# v3s-v0_1_0.net
KiCad netlist of a schematic drawn in EAGLE
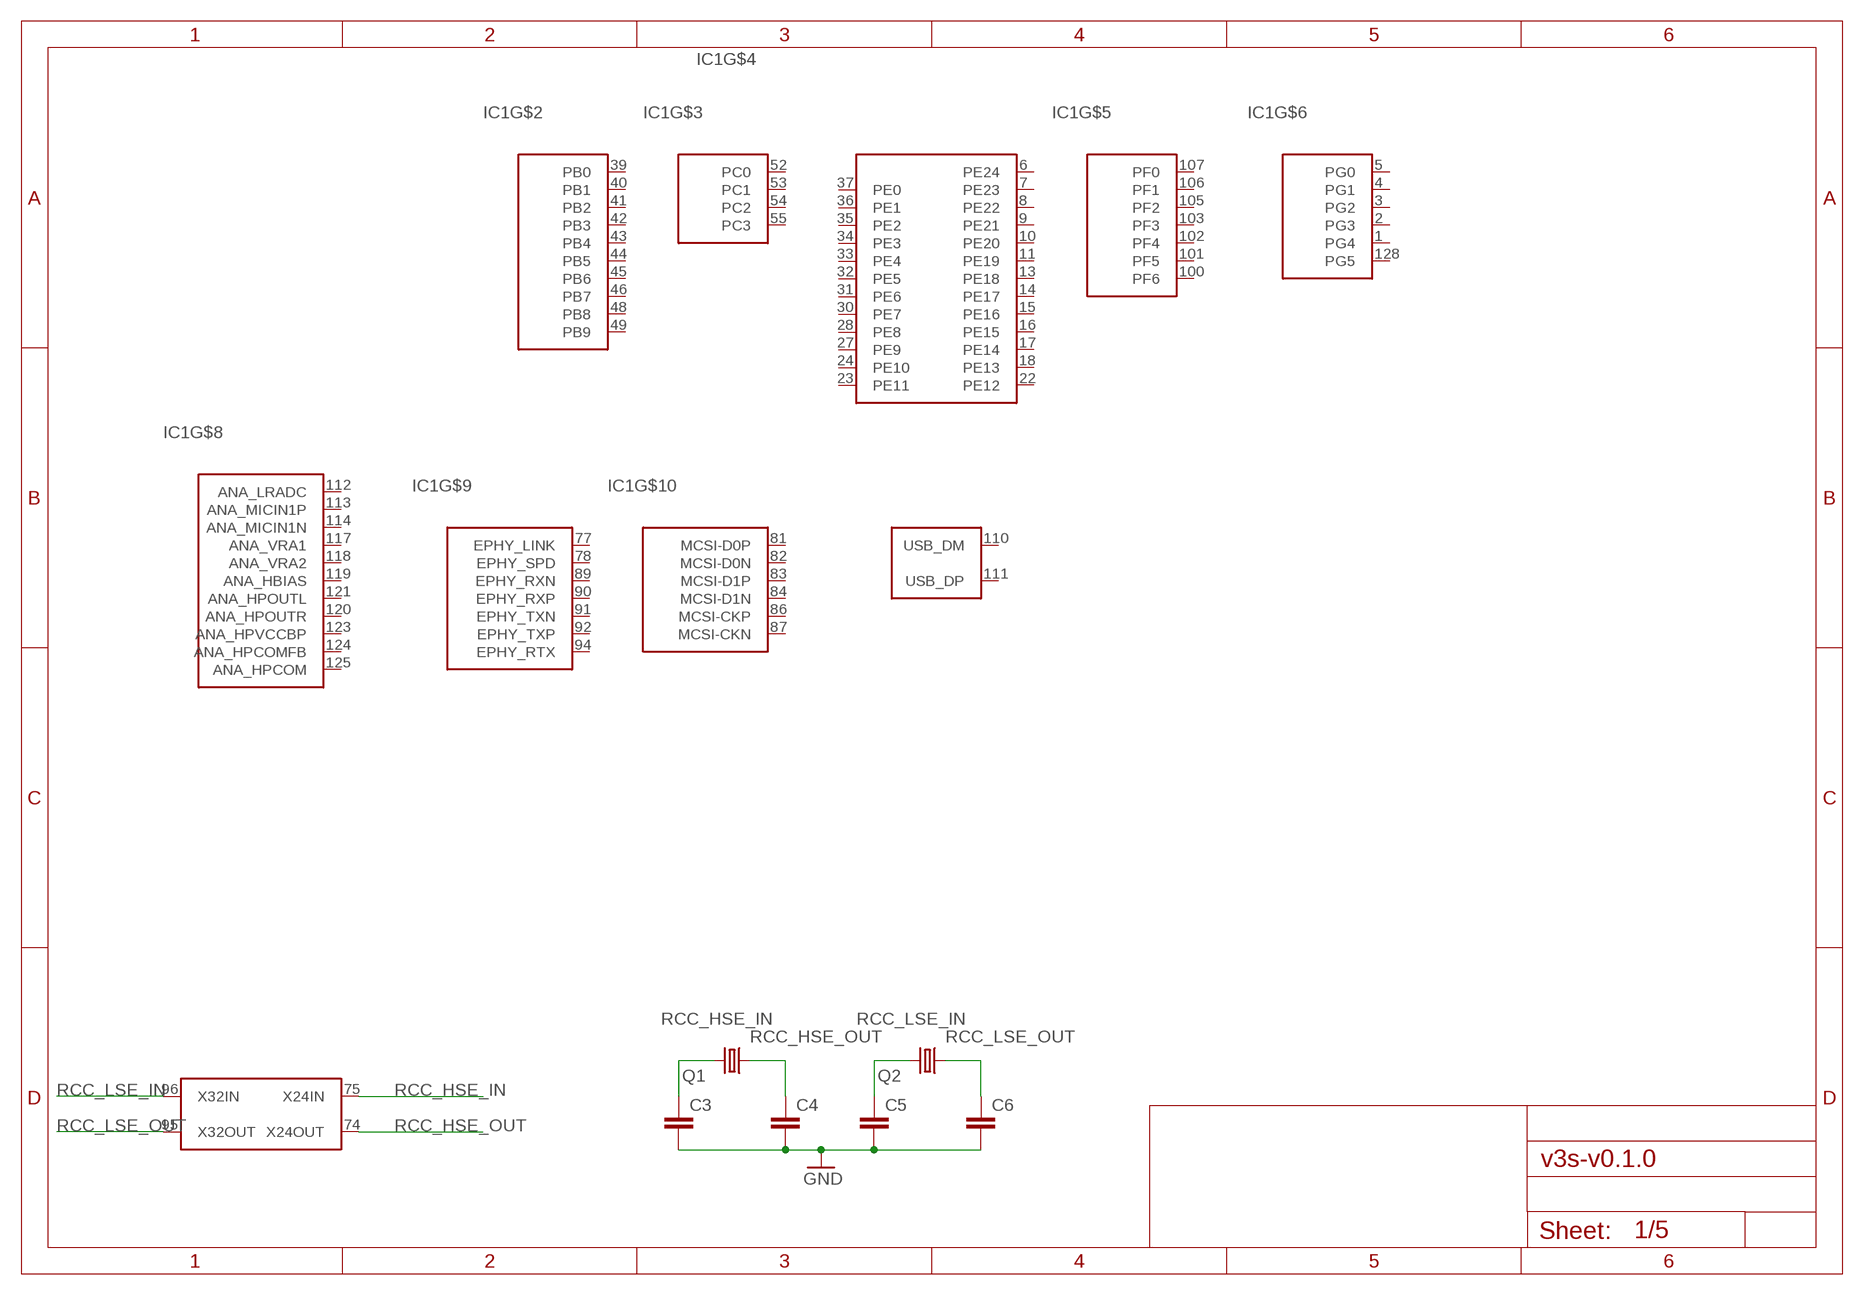
[diagram p0: schematic, sheet 1]
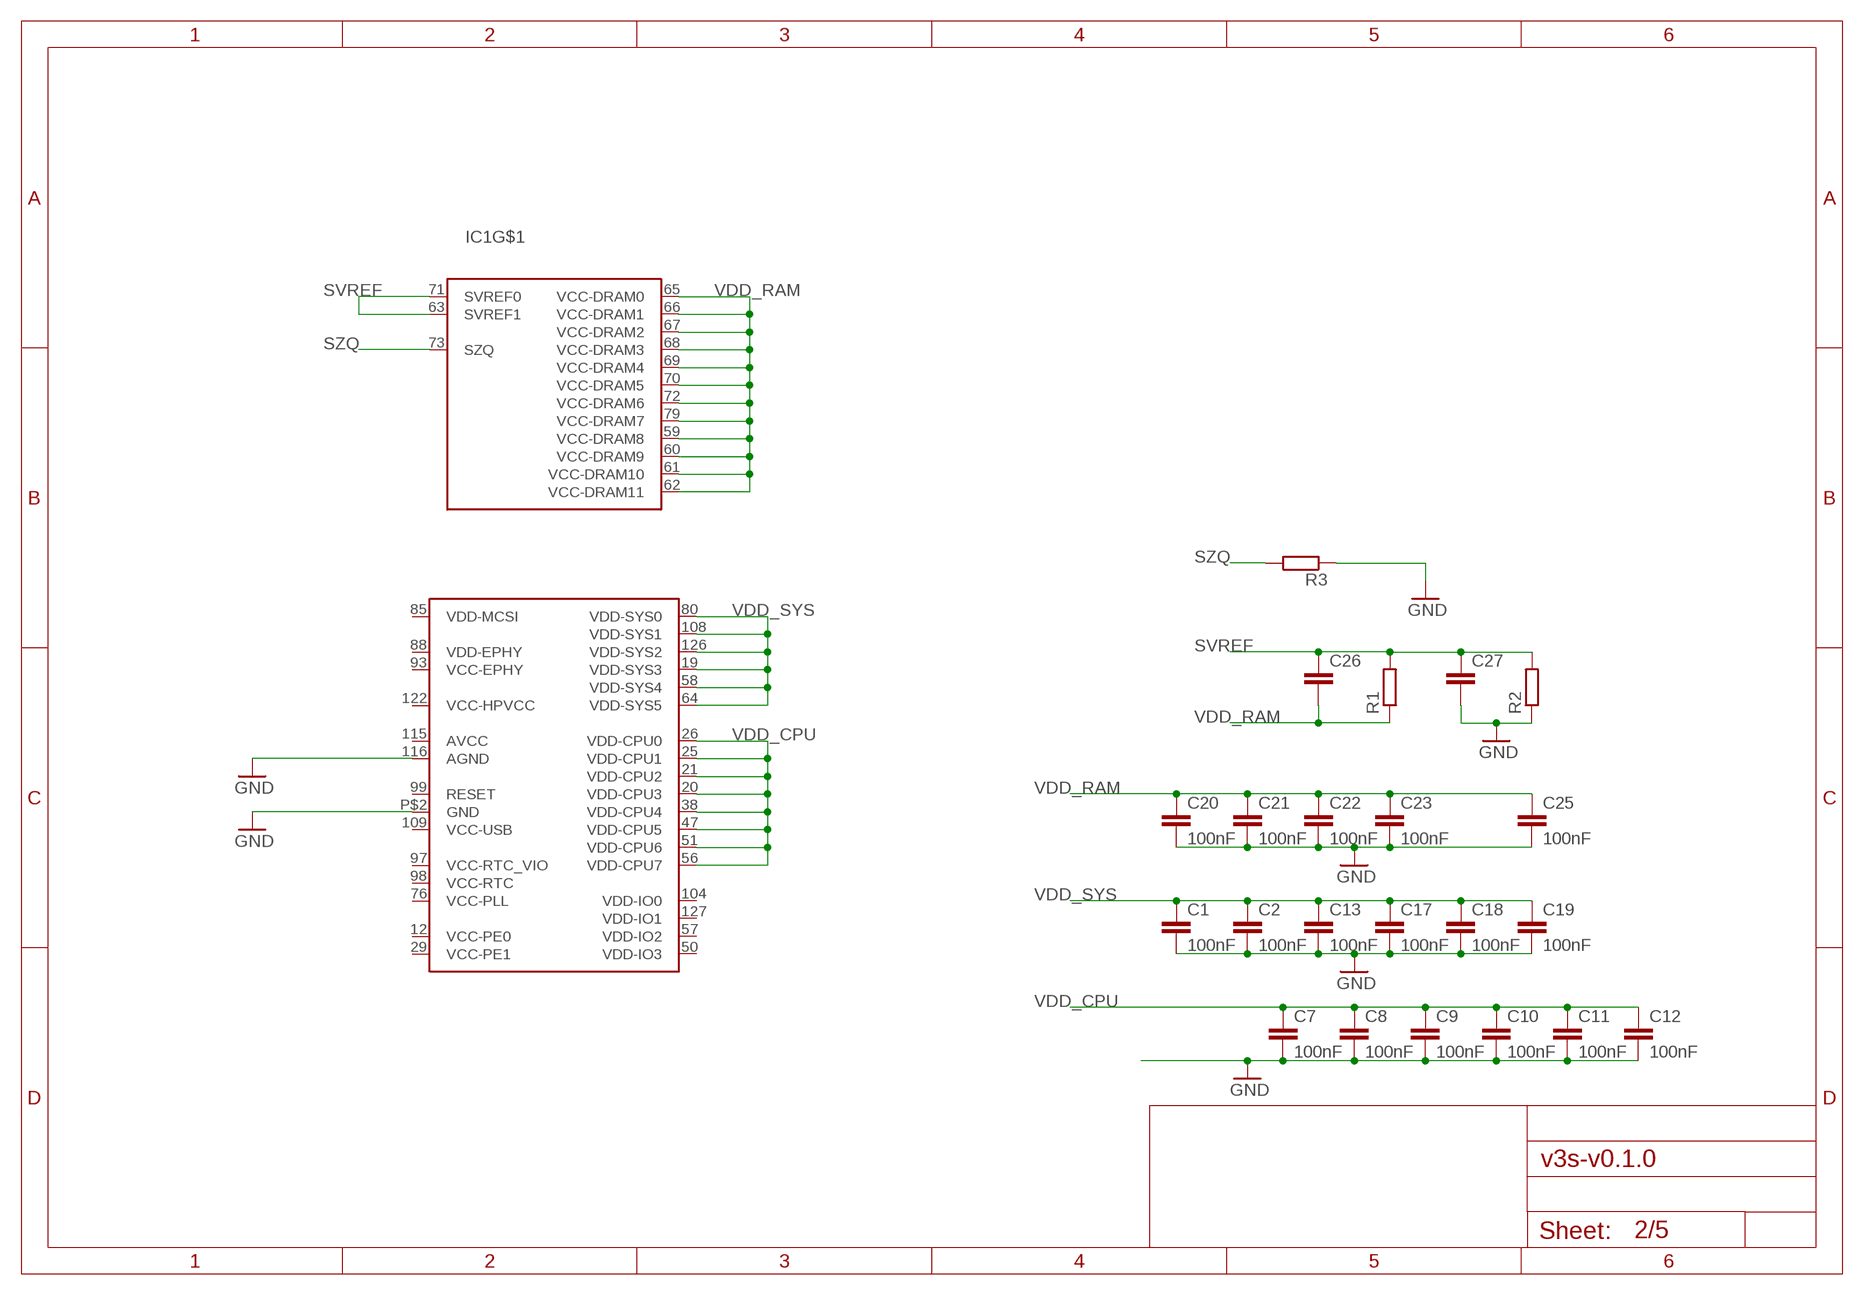
[diagram p1: schematic, sheet 2]
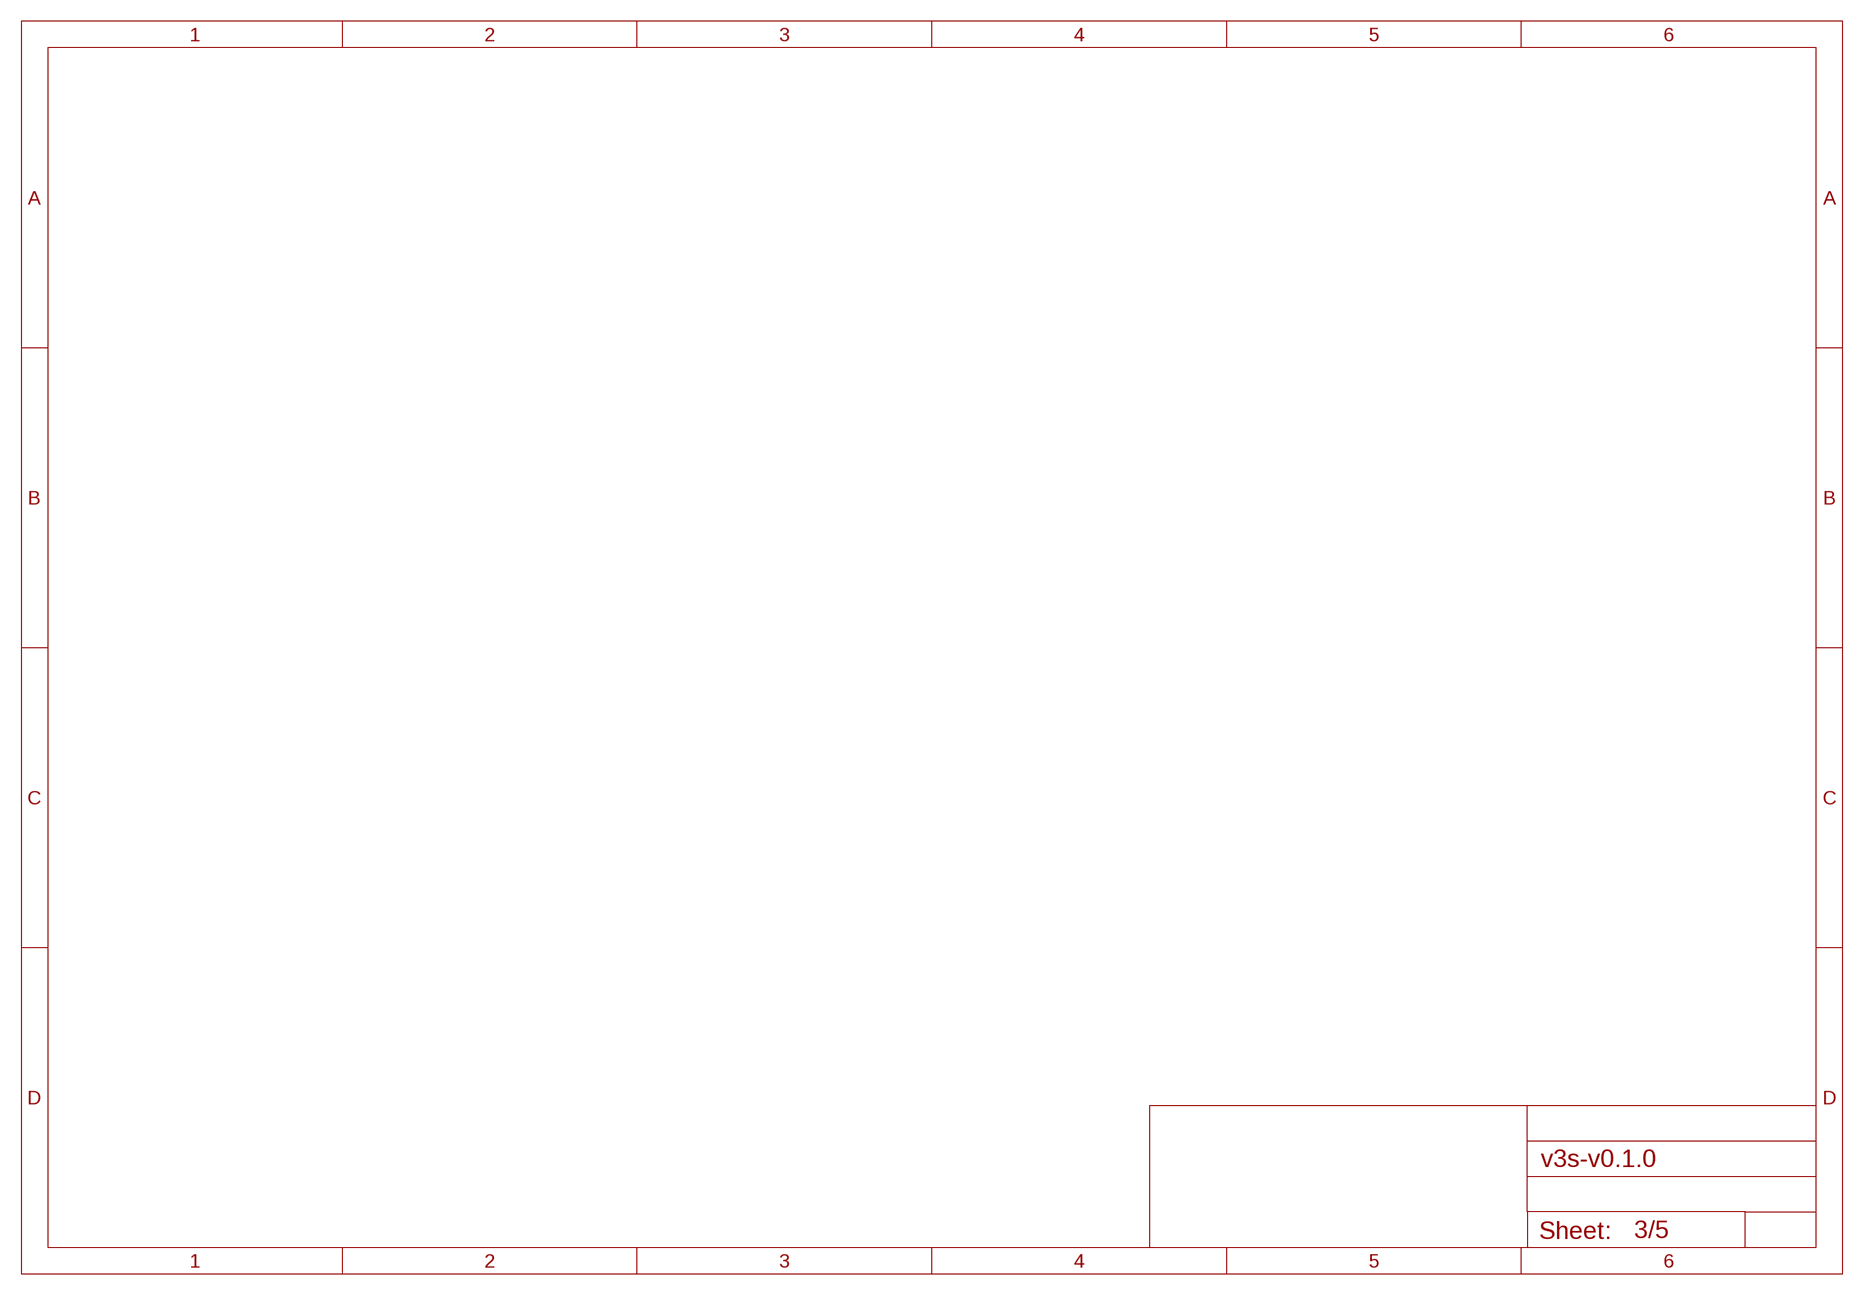
[diagram p2: schematic, sheet 3]
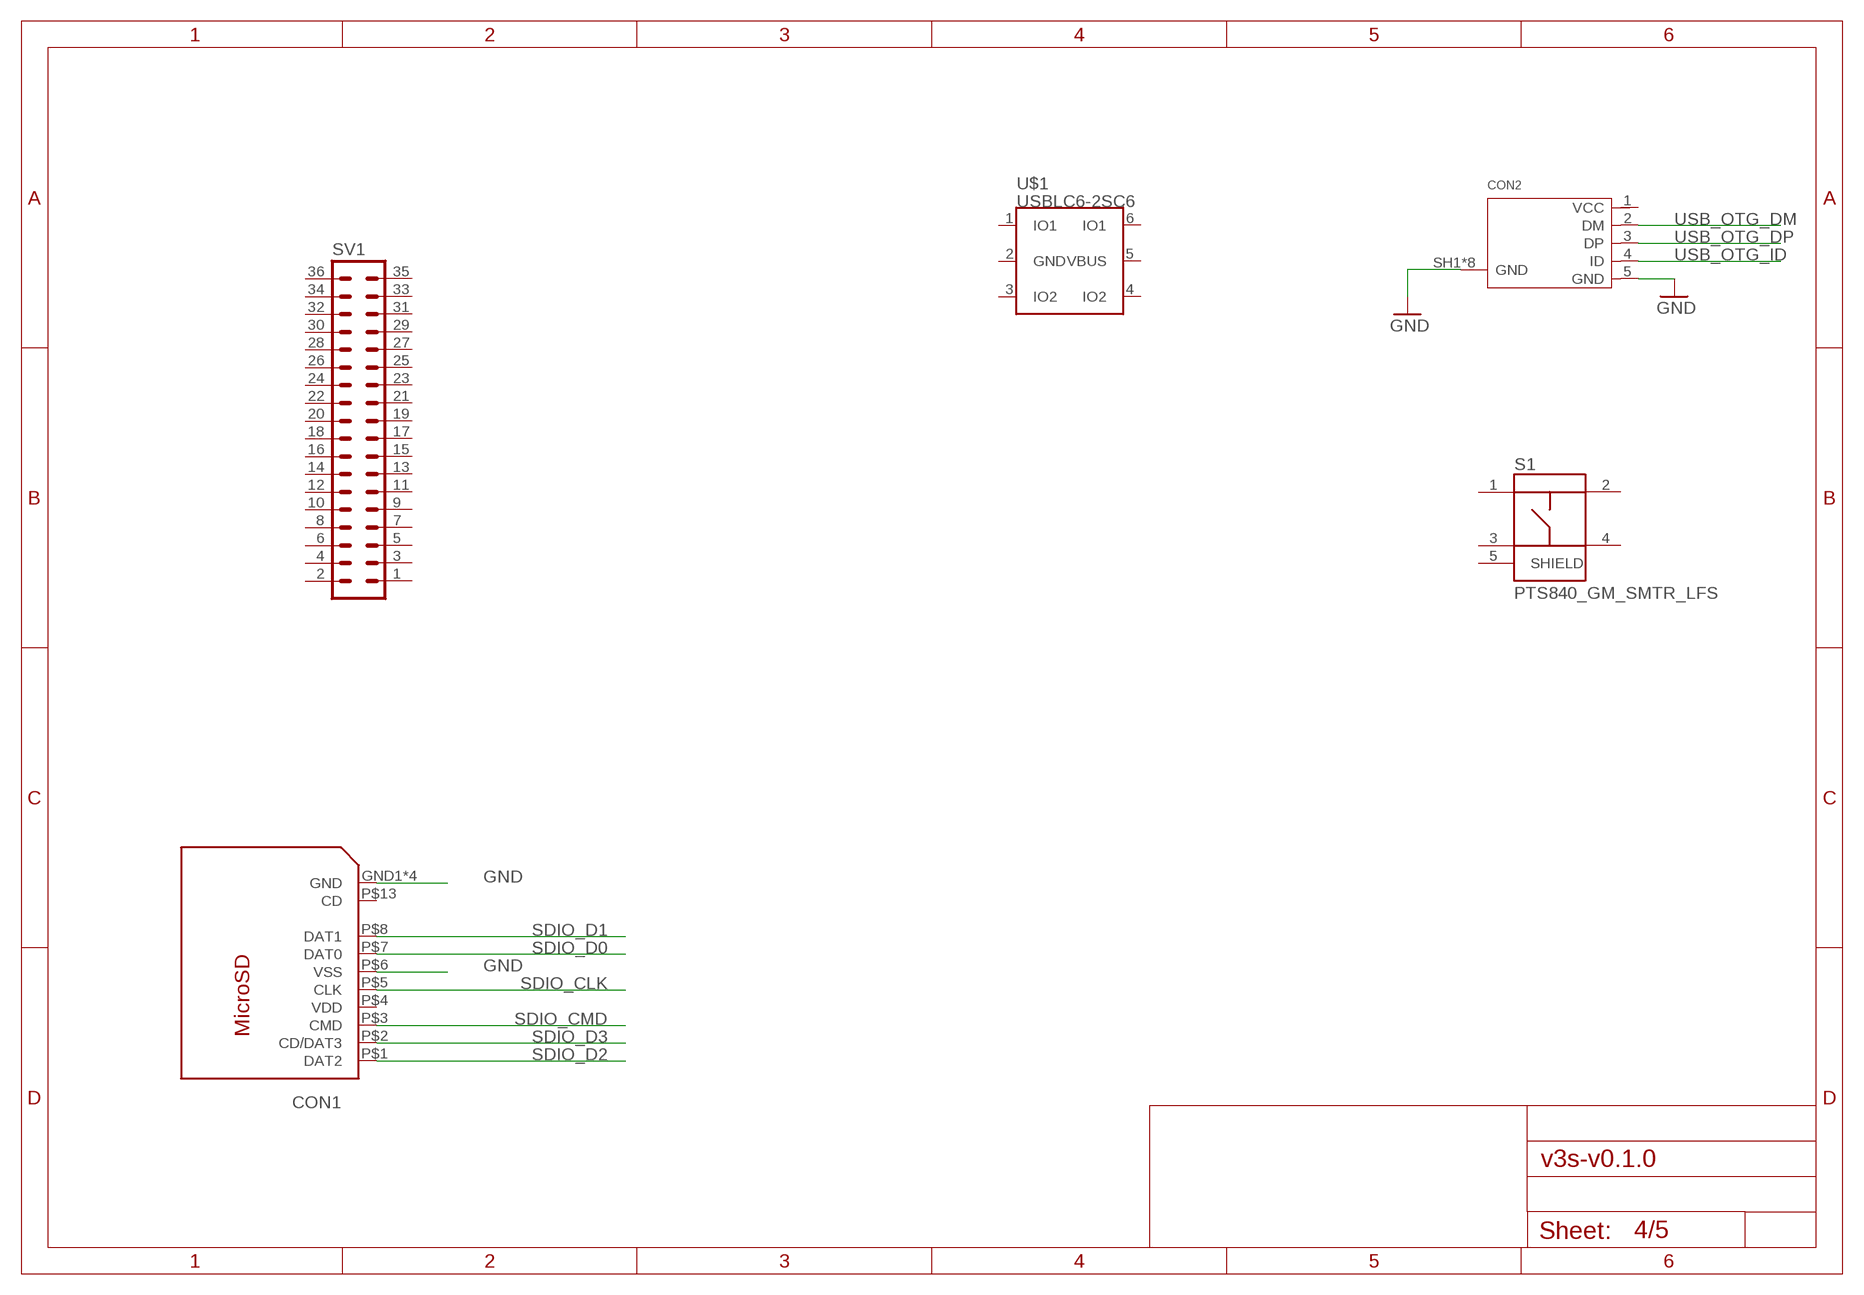
[diagram p3: schematic, sheet 4]
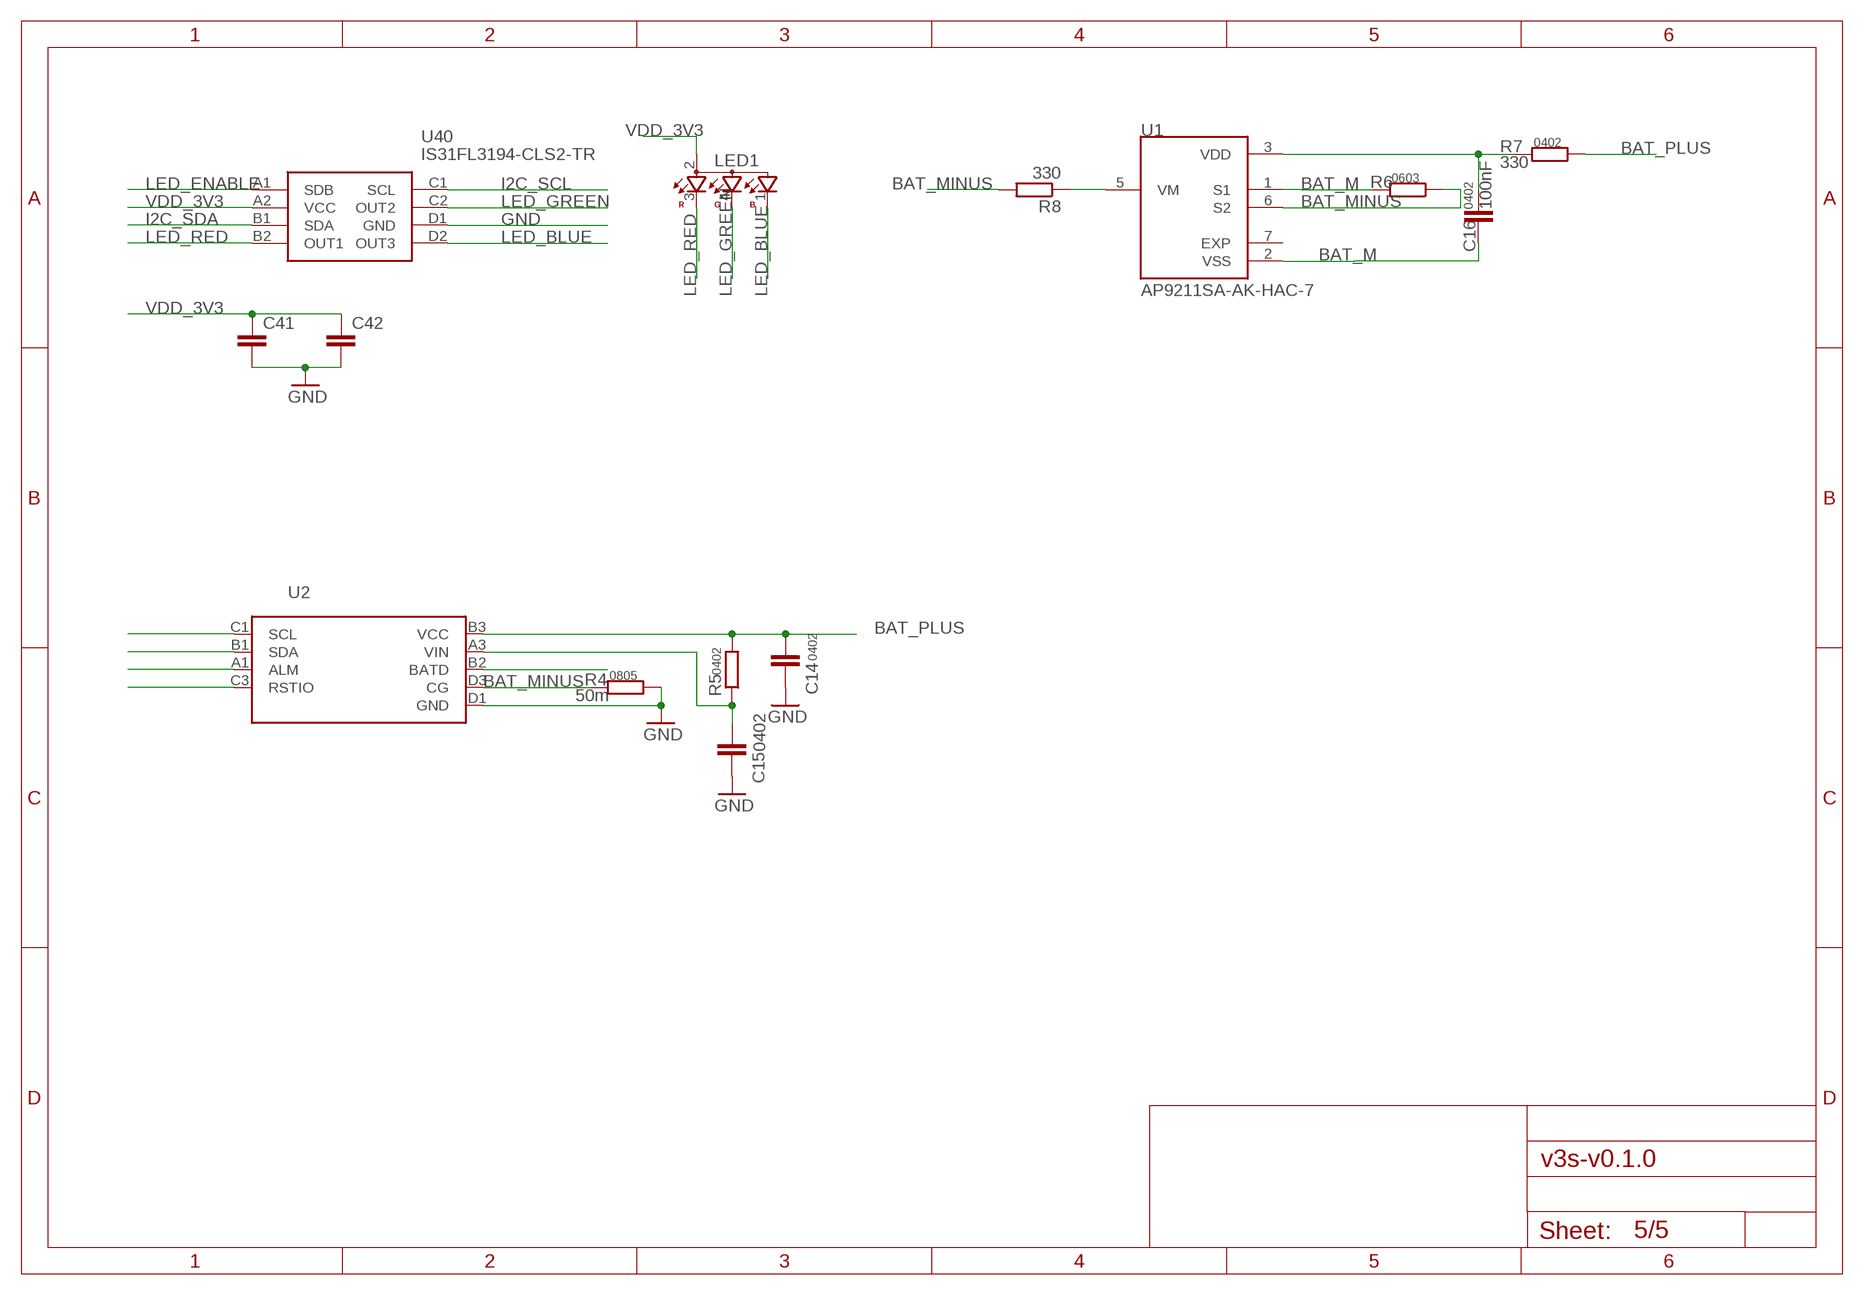
[diagram p4: schematic, sheet 5]

(export (version "E")
  (design (tool "Eeschema 10.0.6"))
  (components
    (comp (ref "CON1")
      (value "112J-TXAR")
      (footprint "eagle-import:112J")
      (libsource (lib "eagle-import") (part "112J-TXAR"))
    )
    (comp (ref "CON2")
      (value "10118194-0001LF")
      (footprint "eagle-import:10118194")
      (libsource (lib "eagle-import") (part "10118194-0001LF"))
    )
    (comp (ref "S1")
      (value "PTS840_GM_SMTR_LFS")
      (footprint "eagle-import:SW_PTS840GMSMTRLFS")
      (fields (field (name "MF") "C&K") (field (name "MP") "PTS840 GM SMTR LFS"))
      (libsource (lib "eagle-import") (part "PTS840_GM_SMTR_LFS"))
    )
    (comp (ref "SV1")
      (value "MA18-2")
      (footprint "eagle-import:MA18-2")
      (libsource (lib "eagle-import") (part "MA18-2"))
    )
    (comp (ref "U$1")
      (value "USBLC6-2SC6")
      (footprint "eagle-import:SOT95P280X110-6")
      (libsource (lib "eagle-import") (part "USBLC6-2SC6"))
    )
    (comp (ref "C1")
      (value "100nF")
      (footprint "eagle-import:C0402")
      (libsource (lib "eagle-import") (part "C-EUC0402"))
    )
    (comp (ref "C2")
      (value "100nF")
      (footprint "eagle-import:C0402")
      (libsource (lib "eagle-import") (part "C-EUC0402"))
    )
    (comp (ref "C7")
      (value "100nF")
      (footprint "eagle-import:C0402")
      (libsource (lib "eagle-import") (part "C-EUC0402"))
    )
    (comp (ref "C8")
      (value "100nF")
      (footprint "eagle-import:C0402")
      (libsource (lib "eagle-import") (part "C-EUC0402"))
    )
    (comp (ref "C9")
      (value "100nF")
      (footprint "eagle-import:C0402")
      (libsource (lib "eagle-import") (part "C-EUC0402"))
    )
    (comp (ref "C10")
      (value "100nF")
      (footprint "eagle-import:C0402")
      (libsource (lib "eagle-import") (part "C-EUC0402"))
    )
    (comp (ref "C11")
      (value "100nF")
      (footprint "eagle-import:C0402")
      (libsource (lib "eagle-import") (part "C-EUC0402"))
    )
    (comp (ref "C12")
      (value "100nF")
      (footprint "eagle-import:C0402")
      (libsource (lib "eagle-import") (part "C-EUC0402"))
    )
    (comp (ref "C13")
      (value "100nF")
      (footprint "eagle-import:C0402")
      (libsource (lib "eagle-import") (part "C-EUC0402"))
    )
    (comp (ref "C17")
      (value "100nF")
      (footprint "eagle-import:C0402")
      (libsource (lib "eagle-import") (part "C-EUC0402"))
    )
    (comp (ref "C18")
      (value "100nF")
      (footprint "eagle-import:C0402")
      (libsource (lib "eagle-import") (part "C-EUC0402"))
    )
    (comp (ref "C19")
      (value "100nF")
      (footprint "eagle-import:C0402")
      (libsource (lib "eagle-import") (part "C-EUC0402"))
    )
    (comp (ref "C20")
      (value "100nF")
      (footprint "eagle-import:C0402")
      (libsource (lib "eagle-import") (part "C-EUC0402"))
    )
    (comp (ref "C21")
      (value "100nF")
      (footprint "eagle-import:C0402")
      (libsource (lib "eagle-import") (part "C-EUC0402"))
    )
    (comp (ref "C22")
      (value "100nF")
      (footprint "eagle-import:C0402")
      (libsource (lib "eagle-import") (part "C-EUC0402"))
    )
    (comp (ref "C23")
      (value "100nF")
      (footprint "eagle-import:C0402")
      (libsource (lib "eagle-import") (part "C-EUC0402"))
    )
    (comp (ref "C25")
      (value "100nF")
      (footprint "eagle-import:C0402")
      (libsource (lib "eagle-import") (part "C-EUC0402"))
    )
    (comp (ref "C26")
      (value "C-EUC0402")
      (footprint "eagle-import:C0402")
      (libsource (lib "eagle-import") (part "C-EUC0402"))
    )
    (comp (ref "C27")
      (value "C-EUC0402")
      (footprint "eagle-import:C0402")
      (libsource (lib "eagle-import") (part "C-EUC0402"))
    )
    (comp (ref "IC1")
      (value "V3S")
      (footprint "eagle-import:QFP-128")
      (libsource (lib "eagle-import") (part "V3S"))
    )
    (comp (ref "R1")
      (value "R-EU_R0402")
      (footprint "eagle-import:R0402")
      (libsource (lib "eagle-import") (part "R-EU_R0402"))
    )
    (comp (ref "R2")
      (value "R-EU_R0402")
      (footprint "eagle-import:R0402")
      (libsource (lib "eagle-import") (part "R-EU_R0402"))
    )
    (comp (ref "R3")
      (value "R-EU_R0402")
      (footprint "eagle-import:R0402")
      (libsource (lib "eagle-import") (part "R-EU_R0402"))
    )
    (comp (ref "C14")
      (value "C-EUC0402")
      (footprint "eagle-import:C0402")
      (libsource (lib "eagle-import") (part "C-EUC0402"))
    )
    (comp (ref "C15")
      (value "C-EUC0402")
      (footprint "eagle-import:C0402")
      (libsource (lib "eagle-import") (part "C-EUC0402"))
    )
    (comp (ref "C16")
      (value "100nF")
      (footprint "eagle-import:C0402")
      (libsource (lib "eagle-import") (part "C-EUC0402"))
    )
    (comp (ref "C41")
      (value "C-EUC0402")
      (footprint "eagle-import:C0402")
      (libsource (lib "eagle-import") (part "C-EUC0402"))
    )
    (comp (ref "C42")
      (value "C-EUC0402")
      (footprint "eagle-import:C0402")
      (libsource (lib "eagle-import") (part "C-EUC0402"))
    )
    (comp (ref "LED1")
      (value "OSTB1204C1E")
      (footprint "eagle-import:321015RGB")
      (libsource (lib "eagle-import") (part "OSTB1204C1E"))
    )
    (comp (ref "R4")
      (value "50m")
      (footprint "eagle-import:R0805")
      (libsource (lib "eagle-import") (part "R-EU_R0805"))
    )
    (comp (ref "R5")
      (value "R-EU_R0402")
      (footprint "eagle-import:R0402")
      (libsource (lib "eagle-import") (part "R-EU_R0402"))
    )
    (comp (ref "R6")
      (value "R-EU_R0603")
      (footprint "eagle-import:R0603")
      (libsource (lib "eagle-import") (part "R-EU_R0603"))
    )
    (comp (ref "R7")
      (value "330")
      (footprint "eagle-import:R0402")
      (libsource (lib "eagle-import") (part "R-EU_R0402"))
    )
    (comp (ref "R8")
      (value "330")
      (footprint "eagle-import:R0402")
      (libsource (lib "eagle-import") (part "R-EU_R0402"))
    )
    (comp (ref "U1")
      (value "AP9211SA-AK-HAC-7")
      (footprint "eagle-import:DFN200X300X60-7N")
      (fields (field (name "MF") "Diodes Inc."))
      (libsource (lib "eagle-import") (part "AP9211SA-AK-HAC-7"))
    )
    (comp (ref "U2")
      (value "STC3115")
      (footprint "eagle-import:BGA12C40P4X3_137X201X65")
      (libsource (lib "eagle-import") (part "STC3115"))
    )
    (comp (ref "U40")
      (value "IS31FL3194-CLS2-TR")
      (footprint "eagle-import:BGA8C40P2X4_99X159X42")
      (fields (field (name "MOUSER_PART_NUMBER") "870-IS31FL3194CLS2TR"))
      (libsource (lib "eagle-import") (part "IS31FL3194-CLS2-TR"))
    )
    (comp (ref "C3")
      (value "C-EUC0402")
      (footprint "eagle-import:C0402")
      (libsource (lib "eagle-import") (part "C-EUC0402"))
    )
    (comp (ref "C4")
      (value "C-EUC0402")
      (footprint "eagle-import:C0402")
      (libsource (lib "eagle-import") (part "C-EUC0402"))
    )
    (comp (ref "C5")
      (value "C-EUC0402")
      (footprint "eagle-import:C0402")
      (libsource (lib "eagle-import") (part "C-EUC0402"))
    )
    (comp (ref "C6")
      (value "C-EUC0402")
      (footprint "eagle-import:C0402")
      (libsource (lib "eagle-import") (part "C-EUC0402"))
    )
    (comp (ref "Q1")
      (value "KX-7")
      (footprint "eagle-import:3.2X2.5_KX-7")
      (libsource (lib "eagle-import") (part "KX-7"))
    )
    (comp (ref "Q2")
      (value "KX-327-NHF")
      (footprint "eagle-import:3.2X1.5")
      (libsource (lib "eagle-import") (part "KX-327-NHF"))
    )
  )
  (nets
    (net (code "1") (name "BAT_M") (class "Default")
      (node (ref "C16") (pin "2") (pinfunction "2_2") (pintype "passive"))
      (node (ref "R6") (pin "2") (pinfunction "2_2") (pintype "passive"))
      (node (ref "U1") (pin "1") (pinfunction "S1_1") (pintype "output"))
      (node (ref "U1") (pin "2") (pinfunction "VSS_2") (pintype "power_in"))
    )
    (net (code "2") (name "BAT_MINUS") (class "Default")
      (node (ref "R4") (pin "2") (pinfunction "2_2") (pintype "passive"))
      (node (ref "R6") (pin "1") (pinfunction "1_1") (pintype "passive"))
      (node (ref "R8") (pin "2") (pinfunction "2_2") (pintype "passive"))
      (node (ref "U1") (pin "6") (pinfunction "S2_6") (pintype "output"))
      (node (ref "U2") (pin "D3") (pinfunction "CG_D3") (pintype "bidirectional"))
    )
    (net (code "3") (name "BAT_PLUS") (class "Default")
      (node (ref "C14") (pin "1") (pinfunction "1_1") (pintype "passive"))
      (node (ref "R5") (pin "2") (pinfunction "2_2") (pintype "passive"))
      (node (ref "R7") (pin "1") (pinfunction "1_1") (pintype "passive"))
      (node (ref "U2") (pin "B3") (pinfunction "VCC_B3") (pintype "bidirectional"))
    )
    (net (code "4") (name "CD") (class "Default")
      (node (ref "CON1") (pin "P$13") (pinfunction "CD_P$13") (pintype "power_in"))
    )
    (net (code "5") (name "EXP") (class "Default")
      (node (ref "U1") (pin "7") (pinfunction "EXP_7") (pintype "power_in"))
    )
    (net (code "6") (name "GND") (class "Default")
      (node (ref "C1") (pin "2") (pinfunction "2_2") (pintype "passive"))
      (node (ref "C10") (pin "2") (pinfunction "2_2") (pintype "passive"))
      (node (ref "C11") (pin "2") (pinfunction "2_2") (pintype "passive"))
      (node (ref "C12") (pin "2") (pinfunction "2_2") (pintype "passive"))
      (node (ref "C13") (pin "2") (pinfunction "2_2") (pintype "passive"))
      (node (ref "C14") (pin "2") (pinfunction "2_2") (pintype "passive"))
      (node (ref "C15") (pin "2") (pinfunction "2_2") (pintype "passive"))
      (node (ref "C17") (pin "2") (pinfunction "2_2") (pintype "passive"))
      (node (ref "C18") (pin "2") (pinfunction "2_2") (pintype "passive"))
      (node (ref "C19") (pin "2") (pinfunction "2_2") (pintype "passive"))
      (node (ref "C2") (pin "2") (pinfunction "2_2") (pintype "passive"))
      (node (ref "C20") (pin "2") (pinfunction "2_2") (pintype "passive"))
      (node (ref "C21") (pin "2") (pinfunction "2_2") (pintype "passive"))
      (node (ref "C22") (pin "2") (pinfunction "2_2") (pintype "passive"))
      (node (ref "C23") (pin "2") (pinfunction "2_2") (pintype "passive"))
      (node (ref "C25") (pin "2") (pinfunction "2_2") (pintype "passive"))
      (node (ref "C27") (pin "2") (pinfunction "2_2") (pintype "passive"))
      (node (ref "C3") (pin "2") (pinfunction "2_2") (pintype "passive"))
      (node (ref "C4") (pin "2") (pinfunction "2_2") (pintype "passive"))
      (node (ref "C41") (pin "2") (pinfunction "2_2") (pintype "passive"))
      (node (ref "C42") (pin "2") (pinfunction "2_2") (pintype "passive"))
      (node (ref "C5") (pin "2") (pinfunction "2_2") (pintype "passive"))
      (node (ref "C6") (pin "2") (pinfunction "2_2") (pintype "passive"))
      (node (ref "C7") (pin "2") (pinfunction "2_2") (pintype "passive"))
      (node (ref "C8") (pin "2") (pinfunction "2_2") (pintype "passive"))
      (node (ref "C9") (pin "2") (pinfunction "2_2") (pintype "passive"))
      (node (ref "CON1") (pin "GND1") (pinfunction "GND_GND1") (pintype "power_in"))
      (node (ref "CON1") (pin "GND2") (pinfunction "GND_GND2") (pintype "power_in"))
      (node (ref "CON1") (pin "GND3") (pinfunction "GND_GND3") (pintype "power_in"))
      (node (ref "CON1") (pin "GND4") (pinfunction "GND_GND4") (pintype "power_in"))
      (node (ref "CON1") (pin "P$6") (pinfunction "VSS_P$6") (pintype "bidirectional"))
      (node (ref "CON2") (pin "5") (pinfunction "GND_5") (pintype "bidirectional"))
      (node (ref "CON2") (pin "SH1") (pinfunction "GND_SH1") (pintype "bidirectional"))
      (node (ref "CON2") (pin "SH2") (pinfunction "GND_SH2") (pintype "bidirectional"))
      (node (ref "CON2") (pin "SH3") (pinfunction "GND_SH3") (pintype "bidirectional"))
      (node (ref "CON2") (pin "SH4") (pinfunction "GND_SH4") (pintype "bidirectional"))
      (node (ref "CON2") (pin "SH5") (pinfunction "GND_SH5") (pintype "bidirectional"))
      (node (ref "CON2") (pin "SH6") (pinfunction "GND_SH6") (pintype "bidirectional"))
      (node (ref "CON2") (pin "SH7") (pinfunction "GND_SH7") (pintype "bidirectional"))
      (node (ref "CON2") (pin "SH8") (pinfunction "GND_SH8") (pintype "bidirectional"))
      (node (ref "IC1") (pin "116") (pinfunction "AGND_116") (pintype "bidirectional"))
      (node (ref "IC1") (pin "P$2") (pinfunction "GND_P$2") (pintype "bidirectional"))
      (node (ref "R2") (pin "1") (pinfunction "1_1") (pintype "passive"))
      (node (ref "R3") (pin "1") (pinfunction "1_1") (pintype "passive"))
      (node (ref "R4") (pin "1") (pinfunction "1_1") (pintype "passive"))
      (node (ref "U2") (pin "D1") (pinfunction "GND_D1") (pintype "bidirectional"))
      (node (ref "U40") (pin "D1") (pinfunction "GND_D1") (pintype "bidirectional"))
    )
    (net (code "7") (name "I2C_SCL") (class "Default")
      (node (ref "U40") (pin "C1") (pinfunction "SCL_C1") (pintype "bidirectional"))
    )
    (net (code "8") (name "I2C_SDA") (class "Default")
      (node (ref "U40") (pin "B1") (pinfunction "SDA_B1") (pintype "bidirectional"))
    )
    (net (code "9") (name "LED_BLUE") (class "Default")
      (node (ref "LED1") (pin "1") (pinfunction "1_1") (pintype "passive"))
      (node (ref "U40") (pin "D2") (pinfunction "OUT3_D2") (pintype "bidirectional"))
    )
    (net (code "10") (name "LED_ENABLE") (class "Default")
      (node (ref "U40") (pin "A1") (pinfunction "SDB_A1") (pintype "bidirectional"))
    )
    (net (code "11") (name "LED_GREEN") (class "Default")
      (node (ref "LED1") (pin "4") (pinfunction "4_4") (pintype "passive"))
      (node (ref "U40") (pin "C2") (pinfunction "OUT2_C2") (pintype "bidirectional"))
    )
    (net (code "12") (name "LED_RED") (class "Default")
      (node (ref "LED1") (pin "3") (pinfunction "3_3") (pintype "passive"))
      (node (ref "U40") (pin "B2") (pinfunction "OUT1_B2") (pintype "bidirectional"))
    )
    (net (code "13") (name "Net-(U1-VDD)") (class "Default")
      (node (ref "C16") (pin "1") (pinfunction "1_1") (pintype "passive"))
      (node (ref "R7") (pin "2") (pinfunction "2_2") (pintype "passive"))
      (node (ref "U1") (pin "3") (pinfunction "VDD_3") (pintype "power_in"))
    )
    (net (code "14") (name "Net-(U1-VM)") (class "Default")
      (node (ref "R8") (pin "1") (pinfunction "1_1") (pintype "passive"))
      (node (ref "U1") (pin "5") (pinfunction "VM_5") (pintype "input"))
    )
    (net (code "15") (name "Net-(U2-VIN)") (class "Default")
      (node (ref "C15") (pin "1") (pinfunction "1_1") (pintype "passive"))
      (node (ref "R5") (pin "1") (pinfunction "1_1") (pintype "passive"))
      (node (ref "U2") (pin "A3") (pinfunction "VIN_A3") (pintype "bidirectional"))
    )
    (net (code "16") (name "RCC_HSE_IN") (class "Default")
      (node (ref "C3") (pin "1") (pinfunction "1_1") (pintype "passive"))
      (node (ref "IC1") (pin "75") (pinfunction "X24IN_75") (pintype "bidirectional"))
      (node (ref "Q1") (pin "3") (pinfunction "2_3") (pintype "passive"))
    )
    (net (code "17") (name "RCC_HSE_OUT") (class "Default")
      (node (ref "C4") (pin "1") (pinfunction "1_1") (pintype "passive"))
      (node (ref "IC1") (pin "74") (pinfunction "X24OUT_74") (pintype "bidirectional"))
      (node (ref "Q1") (pin "1") (pinfunction "1_1") (pintype "passive"))
    )
    (net (code "18") (name "RCC_LSE_IN") (class "Default")
      (node (ref "C5") (pin "1") (pinfunction "1_1") (pintype "passive"))
      (node (ref "IC1") (pin "96") (pinfunction "X32IN_96") (pintype "bidirectional"))
      (node (ref "Q2") (pin "2") (pinfunction "2_2") (pintype "passive"))
    )
    (net (code "19") (name "RCC_LSE_OUT") (class "Default")
      (node (ref "C6") (pin "1") (pinfunction "1_1") (pintype "passive"))
      (node (ref "IC1") (pin "95") (pinfunction "X32OUT_95") (pintype "bidirectional"))
      (node (ref "Q2") (pin "1") (pinfunction "1_1") (pintype "passive"))
    )
    (net (code "20") (name "SDIO_CLK") (class "Default")
      (node (ref "CON1") (pin "P$5") (pinfunction "CLK_P$5") (pintype "bidirectional"))
    )
    (net (code "21") (name "SDIO_CMD") (class "Default")
      (node (ref "CON1") (pin "P$3") (pinfunction "CMD_P$3") (pintype "input"))
    )
    (net (code "22") (name "SDIO_D0") (class "Default")
      (node (ref "CON1") (pin "P$7") (pinfunction "DAT0_P$7") (pintype "power_in"))
    )
    (net (code "23") (name "SDIO_D1") (class "Default")
      (node (ref "CON1") (pin "P$8") (pinfunction "DAT1_P$8") (pintype "power_in"))
    )
    (net (code "24") (name "SDIO_D2") (class "Default")
      (node (ref "CON1") (pin "P$1") (pinfunction "DAT2_P$1") (pintype "output"))
    )
    (net (code "25") (name "SDIO_D3") (class "Default")
      (node (ref "CON1") (pin "P$2") (pinfunction "CD/DAT3_P$2") (pintype "input"))
    )
    (net (code "26") (name "SVREF") (class "Default")
      (node (ref "C26") (pin "1") (pinfunction "1_1") (pintype "passive"))
      (node (ref "C27") (pin "1") (pinfunction "1_1") (pintype "passive"))
      (node (ref "IC1") (pin "63") (pinfunction "SVREF1_63") (pintype "bidirectional"))
      (node (ref "IC1") (pin "71") (pinfunction "SVREF0_71") (pintype "bidirectional"))
      (node (ref "R1") (pin "2") (pinfunction "2_2") (pintype "passive"))
      (node (ref "R2") (pin "2") (pinfunction "2_2") (pintype "passive"))
    )
    (net (code "27") (name "SZQ") (class "Default")
      (node (ref "IC1") (pin "73") (pinfunction "SZQ_73") (pintype "bidirectional"))
      (node (ref "R3") (pin "2") (pinfunction "2_2") (pintype "passive"))
    )
    (net (code "28") (name "USB_OTG_DM") (class "Default")
      (node (ref "CON2") (pin "2") (pinfunction "DM_2") (pintype "bidirectional"))
    )
    (net (code "29") (name "USB_OTG_DP") (class "Default")
      (node (ref "CON2") (pin "3") (pinfunction "DP_3") (pintype "bidirectional"))
    )
    (net (code "30") (name "USB_OTG_ID") (class "Default")
      (node (ref "CON2") (pin "4") (pinfunction "ID_4") (pintype "bidirectional"))
    )
    (net (code "31") (name "VDD_3V3") (class "Default")
      (node (ref "C41") (pin "1") (pinfunction "1_1") (pintype "passive"))
      (node (ref "C42") (pin "1") (pinfunction "1_1") (pintype "passive"))
      (node (ref "LED1") (pin "2") (pinfunction "2_2") (pintype "passive"))
      (node (ref "U40") (pin "A2") (pinfunction "VCC_A2") (pintype "bidirectional"))
    )
    (net (code "32") (name "VDD_CPU") (class "Default")
      (node (ref "C10") (pin "1") (pinfunction "1_1") (pintype "passive"))
      (node (ref "C11") (pin "1") (pinfunction "1_1") (pintype "passive"))
      (node (ref "C12") (pin "1") (pinfunction "1_1") (pintype "passive"))
      (node (ref "C7") (pin "1") (pinfunction "1_1") (pintype "passive"))
      (node (ref "C8") (pin "1") (pinfunction "1_1") (pintype "passive"))
      (node (ref "C9") (pin "1") (pinfunction "1_1") (pintype "passive"))
      (node (ref "IC1") (pin "20") (pinfunction "VDD-CPU3_20") (pintype "bidirectional"))
      (node (ref "IC1") (pin "21") (pinfunction "VDD-CPU2_21") (pintype "bidirectional"))
      (node (ref "IC1") (pin "25") (pinfunction "VDD-CPU1_25") (pintype "bidirectional"))
      (node (ref "IC1") (pin "26") (pinfunction "VDD-CPU0_26") (pintype "bidirectional"))
      (node (ref "IC1") (pin "38") (pinfunction "VDD-CPU4_38") (pintype "bidirectional"))
      (node (ref "IC1") (pin "47") (pinfunction "VDD-CPU5_47") (pintype "bidirectional"))
      (node (ref "IC1") (pin "51") (pinfunction "VDD-CPU6_51") (pintype "bidirectional"))
      (node (ref "IC1") (pin "56") (pinfunction "VDD-CPU7_56") (pintype "bidirectional"))
    )
    (net (code "33") (name "VDD_RAM") (class "Default")
      (node (ref "C20") (pin "1") (pinfunction "1_1") (pintype "passive"))
      (node (ref "C21") (pin "1") (pinfunction "1_1") (pintype "passive"))
      (node (ref "C22") (pin "1") (pinfunction "1_1") (pintype "passive"))
      (node (ref "C23") (pin "1") (pinfunction "1_1") (pintype "passive"))
      (node (ref "C25") (pin "1") (pinfunction "1_1") (pintype "passive"))
      (node (ref "C26") (pin "2") (pinfunction "2_2") (pintype "passive"))
      (node (ref "IC1") (pin "59") (pinfunction "VCC-DRAM8_59") (pintype "bidirectional"))
      (node (ref "IC1") (pin "60") (pinfunction "VCC-DRAM9_60") (pintype "bidirectional"))
      (node (ref "IC1") (pin "61") (pinfunction "VCC-DRAM10_61") (pintype "bidirectional"))
      (node (ref "IC1") (pin "62") (pinfunction "VCC-DRAM11_62") (pintype "bidirectional"))
      (node (ref "IC1") (pin "65") (pinfunction "VCC-DRAM0_65") (pintype "bidirectional"))
      (node (ref "IC1") (pin "66") (pinfunction "VCC-DRAM1_66") (pintype "bidirectional"))
      (node (ref "IC1") (pin "67") (pinfunction "VCC-DRAM2_67") (pintype "bidirectional"))
      (node (ref "IC1") (pin "68") (pinfunction "VCC-DRAM3_68") (pintype "bidirectional"))
      (node (ref "IC1") (pin "69") (pinfunction "VCC-DRAM4_69") (pintype "bidirectional"))
      (node (ref "IC1") (pin "70") (pinfunction "VCC-DRAM5_70") (pintype "bidirectional"))
      (node (ref "IC1") (pin "72") (pinfunction "VCC-DRAM6_72") (pintype "bidirectional"))
      (node (ref "IC1") (pin "79") (pinfunction "VCC-DRAM7_79") (pintype "bidirectional"))
      (node (ref "R1") (pin "1") (pinfunction "1_1") (pintype "passive"))
    )
    (net (code "34") (name "VDD_SYS") (class "Default")
      (node (ref "C1") (pin "1") (pinfunction "1_1") (pintype "passive"))
      (node (ref "C13") (pin "1") (pinfunction "1_1") (pintype "passive"))
      (node (ref "C17") (pin "1") (pinfunction "1_1") (pintype "passive"))
      (node (ref "C18") (pin "1") (pinfunction "1_1") (pintype "passive"))
      (node (ref "C19") (pin "1") (pinfunction "1_1") (pintype "passive"))
      (node (ref "C2") (pin "1") (pinfunction "1_1") (pintype "passive"))
      (node (ref "IC1") (pin "108") (pinfunction "VDD-SYS1_108") (pintype "bidirectional"))
      (node (ref "IC1") (pin "126") (pinfunction "VDD-SYS2_126") (pintype "bidirectional"))
      (node (ref "IC1") (pin "19") (pinfunction "VDD-SYS3_19") (pintype "bidirectional"))
      (node (ref "IC1") (pin "58") (pinfunction "VDD-SYS4_58") (pintype "bidirectional"))
      (node (ref "IC1") (pin "64") (pinfunction "VDD-SYS5_64") (pintype "bidirectional"))
      (node (ref "IC1") (pin "80") (pinfunction "VDD-SYS0_80") (pintype "bidirectional"))
    )
    (net (code "35") (name "unconnected-(CON1-VDD-PadP$4)") (class "Default")
      (node (ref "CON1") (pin "P$4") (pinfunction "VDD_P$4") (pintype "input"))
    )
    (net (code "36") (name "unconnected-(CON2-VCC-Pad1)") (class "Default")
      (node (ref "CON2") (pin "1") (pinfunction "VCC_1") (pintype "bidirectional"))
    )
    (net (code "37") (name "unconnected-(IC1B-MCSI-CKN-Pad87)") (class "Default")
      (node (ref "IC1") (pin "87") (pinfunction "MCSI-CKN_87") (pintype "bidirectional"))
    )
    (net (code "38") (name "unconnected-(IC1B-MCSI-CKP-Pad86)") (class "Default")
      (node (ref "IC1") (pin "86") (pinfunction "MCSI-CKP_86") (pintype "bidirectional"))
    )
    (net (code "39") (name "unconnected-(IC1B-MCSI-D0N-Pad82)") (class "Default")
      (node (ref "IC1") (pin "82") (pinfunction "MCSI-D0N_82") (pintype "bidirectional"))
    )
    (net (code "40") (name "unconnected-(IC1B-MCSI-D0P-Pad81)") (class "Default")
      (node (ref "IC1") (pin "81") (pinfunction "MCSI-D0P_81") (pintype "bidirectional"))
    )
    (net (code "41") (name "unconnected-(IC1B-MCSI-D1N-Pad84)") (class "Default")
      (node (ref "IC1") (pin "84") (pinfunction "MCSI-D1N_84") (pintype "bidirectional"))
    )
    (net (code "42") (name "unconnected-(IC1B-MCSI-D1P-Pad83)") (class "Default")
      (node (ref "IC1") (pin "83") (pinfunction "MCSI-D1P_83") (pintype "bidirectional"))
    )
    (net (code "43") (name "unconnected-(IC1C-AVCC-Pad115)") (class "Default")
      (node (ref "IC1") (pin "115") (pinfunction "AVCC_115") (pintype "bidirectional"))
    )
    (net (code "44") (name "unconnected-(IC1C-RESET-Pad99)") (class "Default")
      (node (ref "IC1") (pin "99") (pinfunction "RESET_99") (pintype "bidirectional"))
    )
    (net (code "45") (name "unconnected-(IC1C-VCC-EPHY-Pad93)") (class "Default")
      (node (ref "IC1") (pin "93") (pinfunction "VCC-EPHY_93") (pintype "bidirectional"))
    )
    (net (code "46") (name "unconnected-(IC1C-VCC-HPVCC-Pad122)") (class "Default")
      (node (ref "IC1") (pin "122") (pinfunction "VCC-HPVCC_122") (pintype "bidirectional"))
    )
    (net (code "47") (name "unconnected-(IC1C-VCC-PE0-Pad12)") (class "Default")
      (node (ref "IC1") (pin "12") (pinfunction "VCC-PE0_12") (pintype "bidirectional"))
    )
    (net (code "48") (name "unconnected-(IC1C-VCC-PE1-Pad29)") (class "Default")
      (node (ref "IC1") (pin "29") (pinfunction "VCC-PE1_29") (pintype "bidirectional"))
    )
    (net (code "49") (name "unconnected-(IC1C-VCC-PLL-Pad76)") (class "Default")
      (node (ref "IC1") (pin "76") (pinfunction "VCC-PLL_76") (pintype "bidirectional"))
    )
    (net (code "50") (name "unconnected-(IC1C-VCC-RTC-Pad98)") (class "Default")
      (node (ref "IC1") (pin "98") (pinfunction "VCC-RTC_98") (pintype "bidirectional"))
    )
    (net (code "51") (name "unconnected-(IC1C-VCC-RTC_VIO-Pad97)") (class "Default")
      (node (ref "IC1") (pin "97") (pinfunction "VCC-RTC_VIO_97") (pintype "bidirectional"))
    )
    (net (code "52") (name "unconnected-(IC1C-VCC-USB-Pad109)") (class "Default")
      (node (ref "IC1") (pin "109") (pinfunction "VCC-USB_109") (pintype "bidirectional"))
    )
    (net (code "53") (name "unconnected-(IC1C-VDD-EPHY-Pad88)") (class "Default")
      (node (ref "IC1") (pin "88") (pinfunction "VDD-EPHY_88") (pintype "bidirectional"))
    )
    (net (code "54") (name "unconnected-(IC1C-VDD-IO0-Pad104)") (class "Default")
      (node (ref "IC1") (pin "104") (pinfunction "VDD-IO0_104") (pintype "bidirectional"))
    )
    (net (code "55") (name "unconnected-(IC1C-VDD-IO1-Pad127)") (class "Default")
      (node (ref "IC1") (pin "127") (pinfunction "VDD-IO1_127") (pintype "bidirectional"))
    )
    (net (code "56") (name "unconnected-(IC1C-VDD-IO2-Pad57)") (class "Default")
      (node (ref "IC1") (pin "57") (pinfunction "VDD-IO2_57") (pintype "bidirectional"))
    )
    (net (code "57") (name "unconnected-(IC1C-VDD-IO3-Pad50)") (class "Default")
      (node (ref "IC1") (pin "50") (pinfunction "VDD-IO3_50") (pintype "bidirectional"))
    )
    (net (code "58") (name "unconnected-(IC1C-VDD-MCSI-Pad85)") (class "Default")
      (node (ref "IC1") (pin "85") (pinfunction "VDD-MCSI_85") (pintype "bidirectional"))
    )
    (net (code "59") (name "unconnected-(IC1D-USB_DM-Pad110)") (class "Default")
      (node (ref "IC1") (pin "110") (pinfunction "USB_DM_110") (pintype "bidirectional"))
    )
    (net (code "60") (name "unconnected-(IC1D-USB_DP-Pad111)") (class "Default")
      (node (ref "IC1") (pin "111") (pinfunction "USB_DP_111") (pintype "bidirectional"))
    )
    (net (code "61") (name "unconnected-(IC1E-PB0-Pad39)") (class "Default")
      (node (ref "IC1") (pin "39") (pinfunction "PB0_39") (pintype "bidirectional"))
    )
    (net (code "62") (name "unconnected-(IC1E-PB1-Pad40)") (class "Default")
      (node (ref "IC1") (pin "40") (pinfunction "PB1_40") (pintype "bidirectional"))
    )
    (net (code "63") (name "unconnected-(IC1E-PB2-Pad41)") (class "Default")
      (node (ref "IC1") (pin "41") (pinfunction "PB2_41") (pintype "bidirectional"))
    )
    (net (code "64") (name "unconnected-(IC1E-PB3-Pad42)") (class "Default")
      (node (ref "IC1") (pin "42") (pinfunction "PB3_42") (pintype "bidirectional"))
    )
    (net (code "65") (name "unconnected-(IC1E-PB4-Pad43)") (class "Default")
      (node (ref "IC1") (pin "43") (pinfunction "PB4_43") (pintype "bidirectional"))
    )
    (net (code "66") (name "unconnected-(IC1E-PB5-Pad44)") (class "Default")
      (node (ref "IC1") (pin "44") (pinfunction "PB5_44") (pintype "bidirectional"))
    )
    (net (code "67") (name "unconnected-(IC1E-PB6-Pad45)") (class "Default")
      (node (ref "IC1") (pin "45") (pinfunction "PB6_45") (pintype "bidirectional"))
    )
    (net (code "68") (name "unconnected-(IC1E-PB7-Pad46)") (class "Default")
      (node (ref "IC1") (pin "46") (pinfunction "PB7_46") (pintype "bidirectional"))
    )
    (net (code "69") (name "unconnected-(IC1E-PB8-Pad48)") (class "Default")
      (node (ref "IC1") (pin "48") (pinfunction "PB8_48") (pintype "bidirectional"))
    )
    (net (code "70") (name "unconnected-(IC1E-PB9-Pad49)") (class "Default")
      (node (ref "IC1") (pin "49") (pinfunction "PB9_49") (pintype "bidirectional"))
    )
    (net (code "71") (name "unconnected-(IC1F-PC0-Pad52)") (class "Default")
      (node (ref "IC1") (pin "52") (pinfunction "PC0_52") (pintype "bidirectional"))
    )
    (net (code "72") (name "unconnected-(IC1F-PC1-Pad53)") (class "Default")
      (node (ref "IC1") (pin "53") (pinfunction "PC1_53") (pintype "bidirectional"))
    )
    (net (code "73") (name "unconnected-(IC1F-PC2-Pad54)") (class "Default")
      (node (ref "IC1") (pin "54") (pinfunction "PC2_54") (pintype "bidirectional"))
    )
    (net (code "74") (name "unconnected-(IC1F-PC3-Pad55)") (class "Default")
      (node (ref "IC1") (pin "55") (pinfunction "PC3_55") (pintype "bidirectional"))
    )
    (net (code "75") (name "unconnected-(IC1G-PE0-Pad37)") (class "Default")
      (node (ref "IC1") (pin "37") (pinfunction "PE0_37") (pintype "bidirectional"))
    )
    (net (code "76") (name "unconnected-(IC1G-PE1-Pad36)") (class "Default")
      (node (ref "IC1") (pin "36") (pinfunction "PE1_36") (pintype "bidirectional"))
    )
    (net (code "77") (name "unconnected-(IC1G-PE2-Pad35)") (class "Default")
      (node (ref "IC1") (pin "35") (pinfunction "PE2_35") (pintype "bidirectional"))
    )
    (net (code "78") (name "unconnected-(IC1G-PE3-Pad34)") (class "Default")
      (node (ref "IC1") (pin "34") (pinfunction "PE3_34") (pintype "bidirectional"))
    )
    (net (code "79") (name "unconnected-(IC1G-PE4-Pad33)") (class "Default")
      (node (ref "IC1") (pin "33") (pinfunction "PE4_33") (pintype "bidirectional"))
    )
    (net (code "80") (name "unconnected-(IC1G-PE5-Pad32)") (class "Default")
      (node (ref "IC1") (pin "32") (pinfunction "PE5_32") (pintype "bidirectional"))
    )
    (net (code "81") (name "unconnected-(IC1G-PE6-Pad31)") (class "Default")
      (node (ref "IC1") (pin "31") (pinfunction "PE6_31") (pintype "bidirectional"))
    )
    (net (code "82") (name "unconnected-(IC1G-PE7-Pad30)") (class "Default")
      (node (ref "IC1") (pin "30") (pinfunction "PE7_30") (pintype "bidirectional"))
    )
    (net (code "83") (name "unconnected-(IC1G-PE8-Pad28)") (class "Default")
      (node (ref "IC1") (pin "28") (pinfunction "PE8_28") (pintype "bidirectional"))
    )
    (net (code "84") (name "unconnected-(IC1G-PE9-Pad27)") (class "Default")
      (node (ref "IC1") (pin "27") (pinfunction "PE9_27") (pintype "bidirectional"))
    )
    (net (code "85") (name "unconnected-(IC1G-PE10-Pad24)") (class "Default")
      (node (ref "IC1") (pin "24") (pinfunction "PE10_24") (pintype "bidirectional"))
    )
    (net (code "86") (name "unconnected-(IC1G-PE11-Pad23)") (class "Default")
      (node (ref "IC1") (pin "23") (pinfunction "PE11_23") (pintype "bidirectional"))
    )
    (net (code "87") (name "unconnected-(IC1G-PE12-Pad22)") (class "Default")
      (node (ref "IC1") (pin "22") (pinfunction "PE12_22") (pintype "bidirectional"))
    )
    (net (code "88") (name "unconnected-(IC1G-PE13-Pad18)") (class "Default")
      (node (ref "IC1") (pin "18") (pinfunction "PE13_18") (pintype "bidirectional"))
    )
    (net (code "89") (name "unconnected-(IC1G-PE14-Pad17)") (class "Default")
      (node (ref "IC1") (pin "17") (pinfunction "PE14_17") (pintype "bidirectional"))
    )
    (net (code "90") (name "unconnected-(IC1G-PE15-Pad16)") (class "Default")
      (node (ref "IC1") (pin "16") (pinfunction "PE15_16") (pintype "bidirectional"))
    )
    (net (code "91") (name "unconnected-(IC1G-PE16-Pad15)") (class "Default")
      (node (ref "IC1") (pin "15") (pinfunction "PE16_15") (pintype "bidirectional"))
    )
    (net (code "92") (name "unconnected-(IC1G-PE17-Pad14)") (class "Default")
      (node (ref "IC1") (pin "14") (pinfunction "PE17_14") (pintype "bidirectional"))
    )
    (net (code "93") (name "unconnected-(IC1G-PE18-Pad13)") (class "Default")
      (node (ref "IC1") (pin "13") (pinfunction "PE18_13") (pintype "bidirectional"))
    )
    (net (code "94") (name "unconnected-(IC1G-PE19-Pad11)") (class "Default")
      (node (ref "IC1") (pin "11") (pinfunction "PE19_11") (pintype "bidirectional"))
    )
    (net (code "95") (name "unconnected-(IC1G-PE20-Pad10)") (class "Default")
      (node (ref "IC1") (pin "10") (pinfunction "PE20_10") (pintype "bidirectional"))
    )
    (net (code "96") (name "unconnected-(IC1G-PE21-Pad9)") (class "Default")
      (node (ref "IC1") (pin "9") (pinfunction "PE21_9") (pintype "bidirectional"))
    )
    (net (code "97") (name "unconnected-(IC1G-PE22-Pad8)") (class "Default")
      (node (ref "IC1") (pin "8") (pinfunction "PE22_8") (pintype "bidirectional"))
    )
    (net (code "98") (name "unconnected-(IC1G-PE23-Pad7)") (class "Default")
      (node (ref "IC1") (pin "7") (pinfunction "PE23_7") (pintype "bidirectional"))
    )
    (net (code "99") (name "unconnected-(IC1G-PE24-Pad6)") (class "Default")
      (node (ref "IC1") (pin "6") (pinfunction "PE24_6") (pintype "bidirectional"))
    )
    (net (code "100") (name "unconnected-(IC1H-PF0-Pad107)") (class "Default")
      (node (ref "IC1") (pin "107") (pinfunction "PF0_107") (pintype "bidirectional"))
    )
    (net (code "101") (name "unconnected-(IC1H-PF1-Pad106)") (class "Default")
      (node (ref "IC1") (pin "106") (pinfunction "PF1_106") (pintype "bidirectional"))
    )
    (net (code "102") (name "unconnected-(IC1H-PF2-Pad105)") (class "Default")
      (node (ref "IC1") (pin "105") (pinfunction "PF2_105") (pintype "bidirectional"))
    )
    (net (code "103") (name "unconnected-(IC1H-PF3-Pad103)") (class "Default")
      (node (ref "IC1") (pin "103") (pinfunction "PF3_103") (pintype "bidirectional"))
    )
    (net (code "104") (name "unconnected-(IC1H-PF4-Pad102)") (class "Default")
      (node (ref "IC1") (pin "102") (pinfunction "PF4_102") (pintype "bidirectional"))
    )
    (net (code "105") (name "unconnected-(IC1H-PF5-Pad101)") (class "Default")
      (node (ref "IC1") (pin "101") (pinfunction "PF5_101") (pintype "bidirectional"))
    )
    (net (code "106") (name "unconnected-(IC1H-PF6-Pad100)") (class "Default")
      (node (ref "IC1") (pin "100") (pinfunction "PF6_100") (pintype "bidirectional"))
    )
    (net (code "107") (name "unconnected-(IC1I-PG0-Pad5)") (class "Default")
      (node (ref "IC1") (pin "5") (pinfunction "PG0_5") (pintype "bidirectional"))
    )
    (net (code "108") (name "unconnected-(IC1I-PG1-Pad4)") (class "Default")
      (node (ref "IC1") (pin "4") (pinfunction "PG1_4") (pintype "bidirectional"))
    )
    (net (code "109") (name "unconnected-(IC1I-PG2-Pad3)") (class "Default")
      (node (ref "IC1") (pin "3") (pinfunction "PG2_3") (pintype "bidirectional"))
    )
    (net (code "110") (name "unconnected-(IC1I-PG3-Pad2)") (class "Default")
      (node (ref "IC1") (pin "2") (pinfunction "PG3_2") (pintype "bidirectional"))
    )
    (net (code "111") (name "unconnected-(IC1I-PG4-Pad1)") (class "Default")
      (node (ref "IC1") (pin "1") (pinfunction "PG4_1") (pintype "bidirectional"))
    )
    (net (code "112") (name "unconnected-(IC1I-PG5-Pad128)") (class "Default")
      (node (ref "IC1") (pin "128") (pinfunction "PG5_128") (pintype "bidirectional"))
    )
    (net (code "113") (name "unconnected-(IC1K-ANA_HBIAS-Pad119)") (class "Default")
      (node (ref "IC1") (pin "119") (pinfunction "ANA_HBIAS_119") (pintype "bidirectional"))
    )
    (net (code "114") (name "unconnected-(IC1K-ANA_HPCOM-Pad125)") (class "Default")
      (node (ref "IC1") (pin "125") (pinfunction "ANA_HPCOM_125") (pintype "bidirectional"))
    )
    (net (code "115") (name "unconnected-(IC1K-ANA_HPCOMFB-Pad124)") (class "Default")
      (node (ref "IC1") (pin "124") (pinfunction "ANA_HPCOMFB_124") (pintype "bidirectional"))
    )
    (net (code "116") (name "unconnected-(IC1K-ANA_HPOUTL-Pad121)") (class "Default")
      (node (ref "IC1") (pin "121") (pinfunction "ANA_HPOUTL_121") (pintype "bidirectional"))
    )
    (net (code "117") (name "unconnected-(IC1K-ANA_HPOUTR-Pad120)") (class "Default")
      (node (ref "IC1") (pin "120") (pinfunction "ANA_HPOUTR_120") (pintype "bidirectional"))
    )
    (net (code "118") (name "unconnected-(IC1K-ANA_HPVCCBP-Pad123)") (class "Default")
      (node (ref "IC1") (pin "123") (pinfunction "ANA_HPVCCBP_123") (pintype "bidirectional"))
    )
    (net (code "119") (name "unconnected-(IC1K-ANA_LRADC-Pad112)") (class "Default")
      (node (ref "IC1") (pin "112") (pinfunction "ANA_LRADC_112") (pintype "bidirectional"))
    )
    (net (code "120") (name "unconnected-(IC1K-ANA_MICIN1N-Pad114)") (class "Default")
      (node (ref "IC1") (pin "114") (pinfunction "ANA_MICIN1N_114") (pintype "bidirectional"))
    )
    (net (code "121") (name "unconnected-(IC1K-ANA_MICIN1P-Pad113)") (class "Default")
      (node (ref "IC1") (pin "113") (pinfunction "ANA_MICIN1P_113") (pintype "bidirectional"))
    )
    (net (code "122") (name "unconnected-(IC1K-ANA_VRA1-Pad117)") (class "Default")
      (node (ref "IC1") (pin "117") (pinfunction "ANA_VRA1_117") (pintype "bidirectional"))
    )
    (net (code "123") (name "unconnected-(IC1K-ANA_VRA2-Pad118)") (class "Default")
      (node (ref "IC1") (pin "118") (pinfunction "ANA_VRA2_118") (pintype "bidirectional"))
    )
    (net (code "124") (name "unconnected-(IC1L-EPHY_LINK-Pad77)") (class "Default")
      (node (ref "IC1") (pin "77") (pinfunction "EPHY_LINK_77") (pintype "bidirectional"))
    )
    (net (code "125") (name "unconnected-(IC1L-EPHY_RTX-Pad94)") (class "Default")
      (node (ref "IC1") (pin "94") (pinfunction "EPHY_RTX_94") (pintype "bidirectional"))
    )
    (net (code "126") (name "unconnected-(IC1L-EPHY_RXN-Pad89)") (class "Default")
      (node (ref "IC1") (pin "89") (pinfunction "EPHY_RXN_89") (pintype "bidirectional"))
    )
    (net (code "127") (name "unconnected-(IC1L-EPHY_RXP-Pad90)") (class "Default")
      (node (ref "IC1") (pin "90") (pinfunction "EPHY_RXP_90") (pintype "bidirectional"))
    )
    (net (code "128") (name "unconnected-(IC1L-EPHY_SPD-Pad78)") (class "Default")
      (node (ref "IC1") (pin "78") (pinfunction "EPHY_SPD_78") (pintype "bidirectional"))
    )
    (net (code "129") (name "unconnected-(IC1L-EPHY_TXN-Pad91)") (class "Default")
      (node (ref "IC1") (pin "91") (pinfunction "EPHY_TXN_91") (pintype "bidirectional"))
    )
    (net (code "130") (name "unconnected-(IC1L-EPHY_TXP-Pad92)") (class "Default")
      (node (ref "IC1") (pin "92") (pinfunction "EPHY_TXP_92") (pintype "bidirectional"))
    )
    (net (code "131") (name "unconnected-(S1-Pad1)") (class "Default")
      (node (ref "S1") (pin "1") (pinfunction "1_1") (pintype "passive"))
    )
    (net (code "132") (name "unconnected-(S1-Pad2)") (class "Default")
      (node (ref "S1") (pin "2") (pinfunction "2_2") (pintype "passive"))
    )
    (net (code "133") (name "unconnected-(S1-Pad3)") (class "Default")
      (node (ref "S1") (pin "3") (pinfunction "3_3") (pintype "passive"))
    )
    (net (code "134") (name "unconnected-(S1-Pad4)") (class "Default")
      (node (ref "S1") (pin "4") (pinfunction "4_4") (pintype "passive"))
    )
    (net (code "135") (name "unconnected-(S1-SHIELD-Pad5)") (class "Default")
      (node (ref "S1") (pin "5") (pinfunction "SHIELD_5") (pintype "passive"))
    )
    (net (code "136") (name "unconnected-(SV1-Pad1)") (class "Default")
      (node (ref "SV1") (pin "1") (pinfunction "1_1") (pintype "passive"))
    )
    (net (code "137") (name "unconnected-(SV1-Pad2)") (class "Default")
      (node (ref "SV1") (pin "2") (pinfunction "2_2") (pintype "passive"))
    )
    (net (code "138") (name "unconnected-(SV1-Pad3)") (class "Default")
      (node (ref "SV1") (pin "3") (pinfunction "3_3") (pintype "passive"))
    )
    (net (code "139") (name "unconnected-(SV1-Pad4)") (class "Default")
      (node (ref "SV1") (pin "4") (pinfunction "4_4") (pintype "passive"))
    )
    (net (code "140") (name "unconnected-(SV1-Pad5)") (class "Default")
      (node (ref "SV1") (pin "5") (pinfunction "5_5") (pintype "passive"))
    )
    (net (code "141") (name "unconnected-(SV1-Pad6)") (class "Default")
      (node (ref "SV1") (pin "6") (pinfunction "6_6") (pintype "passive"))
    )
    (net (code "142") (name "unconnected-(SV1-Pad7)") (class "Default")
      (node (ref "SV1") (pin "7") (pinfunction "7_7") (pintype "passive"))
    )
    (net (code "143") (name "unconnected-(SV1-Pad8)") (class "Default")
      (node (ref "SV1") (pin "8") (pinfunction "8_8") (pintype "passive"))
    )
    (net (code "144") (name "unconnected-(SV1-Pad9)") (class "Default")
      (node (ref "SV1") (pin "9") (pinfunction "9_9") (pintype "passive"))
    )
    (net (code "145") (name "unconnected-(SV1-Pad10)") (class "Default")
      (node (ref "SV1") (pin "10") (pinfunction "10_10") (pintype "passive"))
    )
    (net (code "146") (name "unconnected-(SV1-Pad11)") (class "Default")
      (node (ref "SV1") (pin "11") (pinfunction "11_11") (pintype "passive"))
    )
    (net (code "147") (name "unconnected-(SV1-Pad12)") (class "Default")
      (node (ref "SV1") (pin "12") (pinfunction "12_12") (pintype "passive"))
    )
    (net (code "148") (name "unconnected-(SV1-Pad13)") (class "Default")
      (node (ref "SV1") (pin "13") (pinfunction "13_13") (pintype "passive"))
    )
    (net (code "149") (name "unconnected-(SV1-Pad14)") (class "Default")
      (node (ref "SV1") (pin "14") (pinfunction "14_14") (pintype "passive"))
    )
    (net (code "150") (name "unconnected-(SV1-Pad15)") (class "Default")
      (node (ref "SV1") (pin "15") (pinfunction "15_15") (pintype "passive"))
    )
    (net (code "151") (name "unconnected-(SV1-Pad16)") (class "Default")
      (node (ref "SV1") (pin "16") (pinfunction "16_16") (pintype "passive"))
    )
    (net (code "152") (name "unconnected-(SV1-Pad17)") (class "Default")
      (node (ref "SV1") (pin "17") (pinfunction "17_17") (pintype "passive"))
    )
    (net (code "153") (name "unconnected-(SV1-Pad18)") (class "Default")
      (node (ref "SV1") (pin "18") (pinfunction "18_18") (pintype "passive"))
    )
    (net (code "154") (name "unconnected-(SV1-Pad19)") (class "Default")
      (node (ref "SV1") (pin "19") (pinfunction "19_19") (pintype "passive"))
    )
    (net (code "155") (name "unconnected-(SV1-Pad20)") (class "Default")
      (node (ref "SV1") (pin "20") (pinfunction "20_20") (pintype "passive"))
    )
    (net (code "156") (name "unconnected-(SV1-Pad21)") (class "Default")
      (node (ref "SV1") (pin "21") (pinfunction "21_21") (pintype "passive"))
    )
    (net (code "157") (name "unconnected-(SV1-Pad22)") (class "Default")
      (node (ref "SV1") (pin "22") (pinfunction "22_22") (pintype "passive"))
    )
    (net (code "158") (name "unconnected-(SV1-Pad23)") (class "Default")
      (node (ref "SV1") (pin "23") (pinfunction "23_23") (pintype "passive"))
    )
    (net (code "159") (name "unconnected-(SV1-Pad24)") (class "Default")
      (node (ref "SV1") (pin "24") (pinfunction "24_24") (pintype "passive"))
    )
    (net (code "160") (name "unconnected-(SV1-Pad25)") (class "Default")
      (node (ref "SV1") (pin "25") (pinfunction "25_25") (pintype "passive"))
    )
    (net (code "161") (name "unconnected-(SV1-Pad26)") (class "Default")
      (node (ref "SV1") (pin "26") (pinfunction "26_26") (pintype "passive"))
    )
    (net (code "162") (name "unconnected-(SV1-Pad27)") (class "Default")
      (node (ref "SV1") (pin "27") (pinfunction "27_27") (pintype "passive"))
    )
    (net (code "163") (name "unconnected-(SV1-Pad28)") (class "Default")
      (node (ref "SV1") (pin "28") (pinfunction "28_28") (pintype "passive"))
    )
    (net (code "164") (name "unconnected-(SV1-Pad29)") (class "Default")
      (node (ref "SV1") (pin "29") (pinfunction "29_29") (pintype "passive"))
    )
    (net (code "165") (name "unconnected-(SV1-Pad30)") (class "Default")
      (node (ref "SV1") (pin "30") (pinfunction "30_30") (pintype "passive"))
    )
    (net (code "166") (name "unconnected-(SV1-Pad31)") (class "Default")
      (node (ref "SV1") (pin "31") (pinfunction "31_31") (pintype "passive"))
    )
    (net (code "167") (name "unconnected-(SV1-Pad32)") (class "Default")
      (node (ref "SV1") (pin "32") (pinfunction "32_32") (pintype "passive"))
    )
    (net (code "168") (name "unconnected-(SV1-Pad33)") (class "Default")
      (node (ref "SV1") (pin "33") (pinfunction "33_33") (pintype "passive"))
    )
    (net (code "169") (name "unconnected-(SV1-Pad34)") (class "Default")
      (node (ref "SV1") (pin "34") (pinfunction "34_34") (pintype "passive"))
    )
    (net (code "170") (name "unconnected-(SV1-Pad35)") (class "Default")
      (node (ref "SV1") (pin "35") (pinfunction "35_35") (pintype "passive"))
    )
    (net (code "171") (name "unconnected-(SV1-Pad36)") (class "Default")
      (node (ref "SV1") (pin "36") (pinfunction "36_36") (pintype "passive"))
    )
    (net (code "172") (name "unconnected-(U$1-GND-Pad2)") (class "Default")
      (node (ref "U$1") (pin "2") (pinfunction "GND_2") (pintype "bidirectional"))
    )
    (net (code "173") (name "unconnected-(U$1-IO1-Pad1)") (class "Default")
      (node (ref "U$1") (pin "1") (pinfunction "IO1_1") (pintype "bidirectional"))
    )
    (net (code "174") (name "unconnected-(U$1-IO1-Pad6)") (class "Default")
      (node (ref "U$1") (pin "6") (pinfunction "IO1_6") (pintype "bidirectional"))
    )
    (net (code "175") (name "unconnected-(U$1-IO2-Pad3)") (class "Default")
      (node (ref "U$1") (pin "3") (pinfunction "IO2_3") (pintype "bidirectional"))
    )
    (net (code "176") (name "unconnected-(U$1-IO2-Pad4)") (class "Default")
      (node (ref "U$1") (pin "4") (pinfunction "IO2_4") (pintype "bidirectional"))
    )
    (net (code "177") (name "unconnected-(U$1-VBUS-Pad5)") (class "Default")
      (node (ref "U$1") (pin "5") (pinfunction "VBUS_5") (pintype "bidirectional"))
    )
    (net (code "178") (name "unconnected-(U2-ALM-PadA1)") (class "Default")
      (node (ref "U2") (pin "A1") (pinfunction "ALM_A1") (pintype "bidirectional"))
    )
    (net (code "179") (name "unconnected-(U2-BATD-PadB2)") (class "Default")
      (node (ref "U2") (pin "B2") (pinfunction "BATD_B2") (pintype "bidirectional"))
    )
    (net (code "180") (name "unconnected-(U2-RSTIO-PadC3)") (class "Default")
      (node (ref "U2") (pin "C3") (pinfunction "RSTIO_C3") (pintype "bidirectional"))
    )
    (net (code "181") (name "unconnected-(U2-SCL-PadC1)") (class "Default")
      (node (ref "U2") (pin "C1") (pinfunction "SCL_C1") (pintype "bidirectional"))
    )
    (net (code "182") (name "unconnected-(U2-SDA-PadB1)") (class "Default")
      (node (ref "U2") (pin "B1") (pinfunction "SDA_B1") (pintype "bidirectional"))
    )
  )
)
